# LEO_COTS_no_mult_rev1.net
KiCad netlist of a schematic drawn in Altium Designer
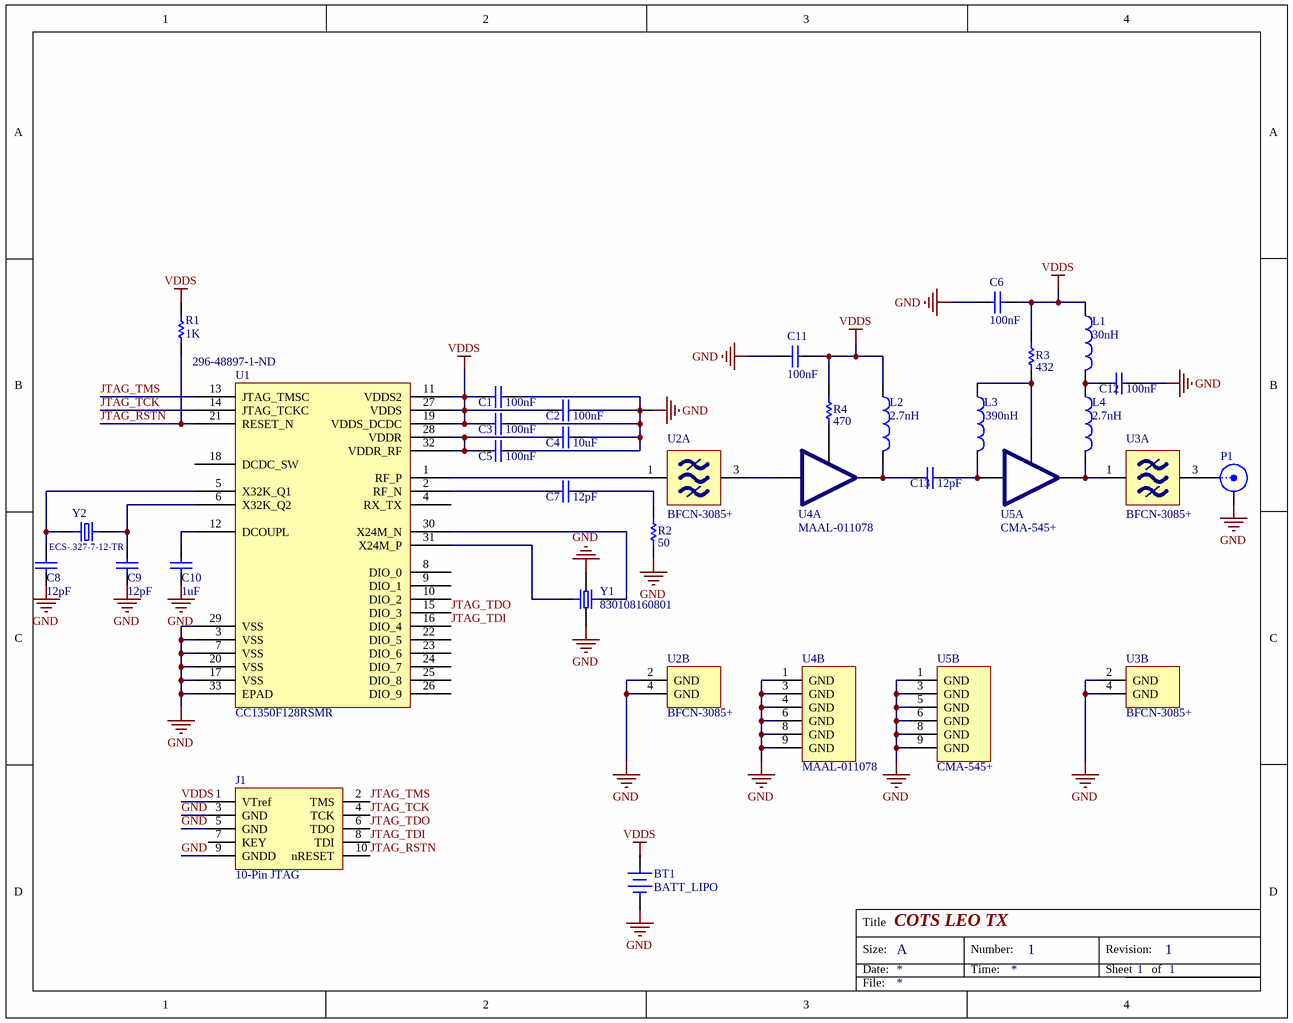
[diagram p0: LEO_COTS_no_mult_rev1.SchDoc]

(export (version "E")
  (design (tool "Eeschema 10.0.6"))
  (components
    (comp (ref "BT1")
      (value "BATT_LIPO")
      (footprint "LIPO_1cm_1cm")
      (libsource (lib "LEO_COTS_components") (part "BATT_LIPO"))
    )
    (comp (ref "C1")
      (value "100nF")
      (footprint "CAPC0603X04N")
      (description "CAP CER 100nF 0201")
      (fields (field (name "Comment") "CAP_0201"))
      (libsource (lib "LEO_COTS_components") (part "CAP_0201"))
    )
    (comp (ref "C2")
      (value "100nF")
      (footprint "CAPC0603X04N")
      (description "CAP CER 100nF 0201")
      (fields (field (name "Comment") "CAP_0201"))
      (libsource (lib "LEO_COTS_components") (part "CAP_0201"))
    )
    (comp (ref "C3")
      (value "100nF")
      (footprint "CAPC0603X04N")
      (description "CAP CER 100nF 0201")
      (fields (field (name "Comment") "CAP_0201"))
      (libsource (lib "LEO_COTS_components") (part "CAP_0201"))
    )
    (comp (ref "C4")
      (value "10uF")
      (footprint "CAPC1608X05N")
      (description "CAP CER 10uF 0603")
      (fields (field (name "Comment") "CAP_0603"))
      (libsource (lib "LEO_COTS_components") (part "CAP_0603"))
    )
    (comp (ref "C5")
      (value "100nF")
      (footprint "CAPC0603X04N")
      (description "CAP CER 100nF 0201")
      (fields (field (name "Comment") "CAP_0201"))
      (libsource (lib "LEO_COTS_components") (part "CAP_0201"))
    )
    (comp (ref "C6")
      (value "100nF")
      (footprint "CAPC0603X04N")
      (description "CAP CER 100nF 0201")
      (fields (field (name "Comment") "CAP_0201"))
      (libsource (lib "LEO_COTS_components") (part "CAP_0201"))
    )
    (comp (ref "C7")
      (value "12pF")
      (footprint "CAPC0603X04N")
      (description "CAP CER 12pF 0201")
      (fields (field (name "Comment") "CAP_0201"))
      (libsource (lib "LEO_COTS_components") (part "CAP_0201"))
    )
    (comp (ref "C8")
      (value "12pF")
      (footprint "CAPC0603X04N")
      (description "CAP CER 12pF 0201")
      (fields (field (name "Comment") "CAP_0201"))
      (libsource (lib "LEO_COTS_components") (part "CAP_0201"))
    )
    (comp (ref "C9")
      (value "12pF")
      (footprint "CAPC0603X04N")
      (description "CAP CER 12pF 0201")
      (fields (field (name "Comment") "CAP_0201"))
      (libsource (lib "LEO_COTS_components") (part "CAP_0201"))
    )
    (comp (ref "C10")
      (value "1uF")
      (footprint "CAPC0603X04N")
      (description "CAP CER 1uF 0201")
      (fields (field (name "Comment") "CAP_0201"))
      (libsource (lib "LEO_COTS_components") (part "CAP_0201"))
    )
    (comp (ref "C11")
      (value "100nF")
      (footprint "CAPC0603X04N")
      (description "CAP CER 100nF 0201")
      (fields (field (name "Comment") "CAP_0201"))
      (libsource (lib "LEO_COTS_components") (part "CAP_0201"))
    )
    (comp (ref "C12")
      (value "100nF")
      (footprint "CAPC0603X04N")
      (description "CAP CER 100nF 0201")
      (fields (field (name "Comment") "CAP_0201"))
      (libsource (lib "LEO_COTS_components") (part "CAP_0201"))
    )
    (comp (ref "C13")
      (value "12pF")
      (footprint "CAPC0603X04N")
      (description "CAP CER 12pF 0201")
      (fields (field (name "Comment") "CAP_0201"))
      (libsource (lib "LEO_COTS_components") (part "CAP_0201"))
    )
    (comp (ref "J1")
      (value "10-Pin JTAG")
      (footprint "FTSH-105-01-F-DV-007-K")
      (description "10-pin JTAG")
      (libsource (lib "LEO_COTS_components") (part "CM10"))
    )
    (comp (ref "L1")
      (value "30nH")
      (footprint "0402")
      (description "Inductor")
      (fields (field (name "PUBLISHER") "Altium Limited"))
      (libsource (lib "LEO_COTS_components") (part "Inductor"))
    )
    (comp (ref "L2")
      (value "2.7nH")
      (footprint "0402")
      (description "Inductor")
      (fields (field (name "PUBLISHER") "Altium Limited"))
      (libsource (lib "LEO_COTS_components") (part "Inductor"))
    )
    (comp (ref "L3")
      (value "390nH")
      (footprint "1608[0603]")
      (description "Inductor")
      (fields (field (name "PUBLISHER") "Altium Limited"))
      (libsource (lib "LEO_COTS_components") (part "Inductor"))
    )
    (comp (ref "L4")
      (value "2.7nH")
      (footprint "0402")
      (description "Inductor")
      (fields (field (name "PUBLISHER") "Altium Limited"))
      (libsource (lib "LEO_COTS_components") (part "Inductor"))
    )
    (comp (ref "P1")
      (value "1909763-1")
      (footprint "1909763-1")
      (description "CONN UMCC JACK STR 50OHM SMD")
      (libsource (lib "LEO_COTS_components") (part "1909763-1"))
    )
    (comp (ref "R1")
      (value "1K")
      (footprint "CAPC0603X04N")
      (description "RES 1K OHM 0201")
      (fields (field (name "Comment") "RES_0201") (field (name "PUBLISHER") "Altium Limited"))
      (libsource (lib "LEO_COTS_components") (part "Res Semi"))
    )
    (comp (ref "R2")
      (value "50")
      (footprint "CAPC0603X04N")
      (description "RES 50 OHM 0201")
      (fields (field (name "Comment") "RES_0201") (field (name "PUBLISHER") "Altium Limited"))
      (libsource (lib "LEO_COTS_components") (part "Res Semi"))
    )
    (comp (ref "R3")
      (value "432")
      (footprint "CAPC0603X04N")
      (description "RES 432 OHM 0201")
      (fields (field (name "Comment") "RES_0201") (field (name "PUBLISHER") "Altium Limited"))
      (libsource (lib "LEO_COTS_components") (part "Res Semi"))
    )
    (comp (ref "R4")
      (value "470")
      (footprint "CAPC0603X04N")
      (description "RES 50 OHM 0201")
      (fields (field (name "Comment") "RES_0201") (field (name "PUBLISHER") "Altium Limited"))
      (libsource (lib "LEO_COTS_components") (part "Res Semi"))
    )
    (comp (ref "U1")
      (value "CC1350F128RSMR")
      (footprint "QFN40P400X400X100-33N")
      (description "Ultra-Low-Power Dual-Band Wireless MCU")
      (fields (field (name "SUPPLIER PART NUMBER 1") "296-48897-1-ND"))
      (libsource (lib "LEO_COTS_components") (part "CC1350F128RSMR"))
    )
    (comp (ref "U2")
      (value "BFCN-3085+")
      (footprint "FV1206")
      (description "2800 to 3400 MHz Band-Pass Filter")
      (libsource (lib "LEO_COTS_components") (part "BFCN-3085+"))
    )
    (comp (ref "U3")
      (value "BFCN-3085+")
      (footprint "FV1206")
      (description "2800 to 3400 MHz Band-Pass Filter")
      (libsource (lib "LEO_COTS_components") (part "BFCN-3085+"))
    )
    (comp (ref "U4")
      (value "MAAL-011078")
      (footprint "PDFN-8")
      (description "Wideband LNA")
      (libsource (lib "LEO_COTS_components") (part "MAAL-011078"))
    )
    (comp (ref "U5")
      (value "CMA-545+")
      (footprint "DL1721")
      (description "Wideband LNA")
      (libsource (lib "LEO_COTS_components") (part "CMA-545+"))
    )
    (comp (ref "Y1")
      (value "830108160801")
      (footprint "LFXTAL081608")
      (description "24 MHz crystal")
      (fields (field (name "MP") "ECS-.327-7-12-TR"))
      (libsource (lib "LEO_COTS_components") (part "830108160801"))
    )
    (comp (ref "Y2")
      (value "ECS-.327-7-12-TR")
      (footprint "XTAL_ECS-.327-7-12-TR")
      (description "32.768 kHz SMD Crystal")
      (libsource (lib "LEO_COTS_components") (part "ECS-.327-7-12-TR"))
    )
  )
  (nets
    (net (code "1") (name "/JTAG_RSTN") (class "Default")
      (node (ref "J1") (pin "10") (pinfunction "nRESET_10") (pintype "passive"))
      (node (ref "R1") (pin "1") (pinfunction "1_1") (pintype "passive"))
      (node (ref "U1") (pin "21") (pinfunction "RESET_N_21") (pintype "passive"))
    )
    (net (code "2") (name "/JTAG_TCK") (class "Default")
      (node (ref "J1") (pin "4") (pinfunction "TCK_4") (pintype "passive"))
      (node (ref "U1") (pin "14") (pinfunction "JTAG_TCKC_14") (pintype "passive"))
    )
    (net (code "3") (name "/JTAG_TDI") (class "Default")
      (node (ref "J1") (pin "8") (pinfunction "TDI_8") (pintype "passive"))
      (node (ref "U1") (pin "16") (pinfunction "DIO_4_16") (pintype "passive"))
    )
    (net (code "4") (name "/JTAG_TDO") (class "Default")
      (node (ref "J1") (pin "6") (pinfunction "TDO_6") (pintype "passive"))
      (node (ref "U1") (pin "15") (pinfunction "DIO_3_15") (pintype "passive"))
    )
    (net (code "5") (name "/JTAG_TMS") (class "Default")
      (node (ref "J1") (pin "2") (pinfunction "TMS_2") (pintype "passive"))
      (node (ref "U1") (pin "13") (pinfunction "JTAG_TMSC_13") (pintype "passive"))
    )
    (net (code "6") (name "GND") (class "Default")
      (node (ref "BT1") (pin "2") (pinfunction "-_2") (pintype "passive"))
      (node (ref "C1") (pin "1") (pinfunction "1_1") (pintype "passive"))
      (node (ref "C10") (pin "1") (pinfunction "1_1") (pintype "passive"))
      (node (ref "C11") (pin "1") (pinfunction "1_1") (pintype "passive"))
      (node (ref "C12") (pin "1") (pinfunction "1_1") (pintype "passive"))
      (node (ref "C2") (pin "1") (pinfunction "1_1") (pintype "passive"))
      (node (ref "C3") (pin "1") (pinfunction "1_1") (pintype "passive"))
      (node (ref "C4") (pin "2") (pinfunction "2_2") (pintype "passive"))
      (node (ref "C5") (pin "1") (pinfunction "1_1") (pintype "passive"))
      (node (ref "C6") (pin "1") (pinfunction "1_1") (pintype "passive"))
      (node (ref "C8") (pin "1") (pinfunction "1_1") (pintype "passive"))
      (node (ref "C9") (pin "1") (pinfunction "1_1") (pintype "passive"))
      (node (ref "J1") (pin "3") (pinfunction "GND_3") (pintype "passive"))
      (node (ref "J1") (pin "5") (pinfunction "GND_5") (pintype "passive"))
      (node (ref "J1") (pin "9") (pinfunction "GNDD_9") (pintype "passive"))
      (node (ref "P1") (pin "2") (pinfunction "Y_2") (pintype "passive"))
      (node (ref "R2") (pin "1") (pinfunction "1_1") (pintype "passive"))
      (node (ref "U1") (pin "17") (pinfunction "VSS_17") (pintype "passive"))
      (node (ref "U1") (pin "20") (pinfunction "VSS_20") (pintype "passive"))
      (node (ref "U1") (pin "29") (pinfunction "VSS_29") (pintype "passive"))
      (node (ref "U1") (pin "3") (pinfunction "VSS_3") (pintype "passive"))
      (node (ref "U1") (pin "33") (pinfunction "EPAD_33") (pintype "passive"))
      (node (ref "U1") (pin "7") (pinfunction "VSS_7") (pintype "passive"))
      (node (ref "U2") (pin "2") (pinfunction "GND_2") (pintype "tri_state"))
      (node (ref "U2") (pin "4") (pinfunction "GND_4") (pintype "tri_state"))
      (node (ref "U3") (pin "2") (pinfunction "GND_2") (pintype "tri_state"))
      (node (ref "U3") (pin "4") (pinfunction "GND_4") (pintype "tri_state"))
      (node (ref "U4") (pin "1") (pinfunction "GND_1") (pintype "tri_state"))
      (node (ref "U4") (pin "3") (pinfunction "GND_3") (pintype "tri_state"))
      (node (ref "U4") (pin "4") (pinfunction "GND_4") (pintype "tri_state"))
      (node (ref "U4") (pin "6") (pinfunction "GND_6") (pintype "tri_state"))
      (node (ref "U4") (pin "8") (pinfunction "GND_8") (pintype "tri_state"))
      (node (ref "U4") (pin "9") (pinfunction "GND_9") (pintype "tri_state"))
      (node (ref "U5") (pin "1") (pinfunction "GND_1") (pintype "tri_state"))
      (node (ref "U5") (pin "3") (pinfunction "GND_3") (pintype "tri_state"))
      (node (ref "U5") (pin "5") (pinfunction "GND_5") (pintype "tri_state"))
      (node (ref "U5") (pin "6") (pinfunction "GND_6") (pintype "tri_state"))
      (node (ref "U5") (pin "8") (pinfunction "GND_8") (pintype "tri_state"))
      (node (ref "U5") (pin "9") (pinfunction "GND_9") (pintype "tri_state"))
      (node (ref "Y1") (pin "2") (pinfunction "2_2") (pintype "passive"))
      (node (ref "Y1") (pin "4") (pinfunction "4_4") (pintype "passive"))
    )
    (net (code "7") (name "Net-(C7-Pad1)") (class "Default")
      (node (ref "C7") (pin "1") (pinfunction "1_1") (pintype "passive"))
      (node (ref "R2") (pin "2") (pinfunction "2_2") (pintype "passive"))
    )
    (net (code "8") (name "Net-(C12-Pad2)") (class "Default")
      (node (ref "C12") (pin "2") (pinfunction "2_2") (pintype "passive"))
      (node (ref "L1") (pin "2") (pinfunction "2_2") (pintype "passive"))
      (node (ref "L4") (pin "1") (pinfunction "1_1") (pintype "passive"))
    )
    (net (code "9") (name "Net-(P1-X)") (class "Default")
      (node (ref "P1") (pin "1") (pinfunction "X_1") (pintype "passive"))
      (node (ref "U3") (pin "3") (pinfunction "OUT_3") (pintype "tri_state"))
    )
    (net (code "10") (name "Net-(U1-DCOUPL)") (class "Default")
      (node (ref "C10") (pin "2") (pinfunction "2_2") (pintype "passive"))
      (node (ref "U1") (pin "12") (pinfunction "DCOUPL_12") (pintype "passive"))
    )
    (net (code "11") (name "Net-(U1-RF_N)") (class "Default")
      (node (ref "C7") (pin "2") (pinfunction "2_2") (pintype "passive"))
      (node (ref "U1") (pin "2") (pinfunction "RF_N_2") (pintype "passive"))
    )
    (net (code "12") (name "Net-(U1-RF_P)") (class "Default")
      (node (ref "U1") (pin "1") (pinfunction "RF_P_1") (pintype "passive"))
      (node (ref "U2") (pin "1") (pinfunction "IN_1") (pintype "tri_state"))
    )
    (net (code "13") (name "Net-(U1-VDDR)") (class "Default")
      (node (ref "C4") (pin "1") (pinfunction "1_1") (pintype "passive"))
      (node (ref "C5") (pin "2") (pinfunction "2_2") (pintype "passive"))
      (node (ref "U1") (pin "28") (pinfunction "VDDR_28") (pintype "passive"))
      (node (ref "U1") (pin "32") (pinfunction "VDDR_RF_32") (pintype "passive"))
    )
    (net (code "14") (name "Net-(U1-X24M_N)") (class "Default")
      (node (ref "U1") (pin "30") (pinfunction "X24M_N_30") (pintype "passive"))
      (node (ref "Y1") (pin "3") (pinfunction "3_3") (pintype "passive"))
    )
    (net (code "15") (name "Net-(U1-X24M_P)") (class "Default")
      (node (ref "U1") (pin "31") (pinfunction "X24M_P_31") (pintype "passive"))
      (node (ref "Y1") (pin "1") (pinfunction "1_1") (pintype "passive"))
    )
    (net (code "16") (name "Net-(U1-X32K_Q1)") (class "Default")
      (node (ref "C8") (pin "2") (pinfunction "2_2") (pintype "passive"))
      (node (ref "U1") (pin "5") (pinfunction "X32K_Q1_5") (pintype "passive"))
      (node (ref "Y2") (pin "1") (pinfunction "1_1") (pintype "passive"))
    )
    (net (code "17") (name "Net-(U1-X32K_Q2)") (class "Default")
      (node (ref "C9") (pin "2") (pinfunction "2_2") (pintype "passive"))
      (node (ref "U1") (pin "6") (pinfunction "X32K_Q2_6") (pintype "passive"))
      (node (ref "Y2") (pin "2") (pinfunction "2_2") (pintype "passive"))
    )
    (net (code "18") (name "Net-(U2A-OUT)") (class "Default")
      (node (ref "U2") (pin "3") (pinfunction "OUT_3") (pintype "tri_state"))
      (node (ref "U4") (pin "2") (pinfunction "IN_2") (pintype "tri_state"))
    )
    (net (code "19") (name "Net-(U3A-IN)") (class "Default")
      (node (ref "L4") (pin "2") (pinfunction "2_2") (pintype "passive"))
      (node (ref "U3") (pin "1") (pinfunction "IN_1") (pintype "tri_state"))
      (node (ref "U5") (pin "7") (pinfunction "OUT_7") (pintype "tri_state"))
    )
    (net (code "20") (name "Net-(U4A-BIAS)") (class "Default")
      (node (ref "R4") (pin "1") (pinfunction "1_1") (pintype "passive"))
      (node (ref "U4") (pin "5") (pinfunction "BIAS_5") (pintype "tri_state"))
    )
    (net (code "21") (name "Net-(U4A-OUT)") (class "Default")
      (node (ref "C13") (pin "2") (pinfunction "2_2") (pintype "passive"))
      (node (ref "L2") (pin "2") (pinfunction "2_2") (pintype "passive"))
      (node (ref "U4") (pin "7") (pinfunction "OUT_7") (pintype "tri_state"))
    )
    (net (code "22") (name "Net-(U5A-BIAS)") (class "Default")
      (node (ref "L3") (pin "1") (pinfunction "1_1") (pintype "passive"))
      (node (ref "R3") (pin "1") (pinfunction "1_1") (pintype "passive"))
      (node (ref "U5") (pin "4") (pinfunction "BIAS_4") (pintype "tri_state"))
    )
    (net (code "23") (name "Net-(U5A-IN)") (class "Default")
      (node (ref "C13") (pin "1") (pinfunction "1_1") (pintype "passive"))
      (node (ref "L3") (pin "2") (pinfunction "2_2") (pintype "passive"))
      (node (ref "U5") (pin "2") (pinfunction "IN_2") (pintype "tri_state"))
    )
    (net (code "24") (name "VDDS") (class "Default")
      (node (ref "BT1") (pin "1") (pinfunction "+_1") (pintype "passive"))
      (node (ref "C1") (pin "2") (pinfunction "2_2") (pintype "passive"))
      (node (ref "C11") (pin "2") (pinfunction "2_2") (pintype "passive"))
      (node (ref "C2") (pin "2") (pinfunction "2_2") (pintype "passive"))
      (node (ref "C3") (pin "2") (pinfunction "2_2") (pintype "passive"))
      (node (ref "C6") (pin "2") (pinfunction "2_2") (pintype "passive"))
      (node (ref "J1") (pin "1") (pinfunction "VTref_1") (pintype "passive"))
      (node (ref "L1") (pin "1") (pinfunction "1_1") (pintype "passive"))
      (node (ref "L2") (pin "1") (pinfunction "1_1") (pintype "passive"))
      (node (ref "R1") (pin "2") (pinfunction "2_2") (pintype "passive"))
      (node (ref "R3") (pin "2") (pinfunction "2_2") (pintype "passive"))
      (node (ref "R4") (pin "2") (pinfunction "2_2") (pintype "passive"))
      (node (ref "U1") (pin "11") (pinfunction "VDDS2_11") (pintype "passive"))
      (node (ref "U1") (pin "19") (pinfunction "VDDS_DCDC_19") (pintype "passive"))
      (node (ref "U1") (pin "27") (pinfunction "VDDS_27") (pintype "passive"))
    )
    (net (code "25") (name "unconnected-(J1-KEY-Pad7)") (class "Default")
      (node (ref "J1") (pin "7") (pinfunction "KEY_7") (pintype "passive"))
    )
    (net (code "26") (name "unconnected-(U1-DCDC_SW-Pad18)") (class "Default")
      (node (ref "U1") (pin "18") (pinfunction "DCDC_SW_18") (pintype "passive"))
    )
    (net (code "27") (name "unconnected-(U1-DIO_0-Pad8)") (class "Default")
      (node (ref "U1") (pin "8") (pinfunction "DIO_0_8") (pintype "passive"))
    )
    (net (code "28") (name "unconnected-(U1-DIO_1-Pad9)") (class "Default")
      (node (ref "U1") (pin "9") (pinfunction "DIO_1_9") (pintype "passive"))
    )
    (net (code "29") (name "unconnected-(U1-DIO_2-Pad10)") (class "Default")
      (node (ref "U1") (pin "10") (pinfunction "DIO_2_10") (pintype "passive"))
    )
    (net (code "30") (name "unconnected-(U1-DIO_5-Pad22)") (class "Default")
      (node (ref "U1") (pin "22") (pinfunction "DIO_5_22") (pintype "passive"))
    )
    (net (code "31") (name "unconnected-(U1-DIO_6-Pad23)") (class "Default")
      (node (ref "U1") (pin "23") (pinfunction "DIO_6_23") (pintype "passive"))
    )
    (net (code "32") (name "unconnected-(U1-DIO_7-Pad24)") (class "Default")
      (node (ref "U1") (pin "24") (pinfunction "DIO_7_24") (pintype "passive"))
    )
    (net (code "33") (name "unconnected-(U1-DIO_8-Pad25)") (class "Default")
      (node (ref "U1") (pin "25") (pinfunction "DIO_8_25") (pintype "passive"))
    )
    (net (code "34") (name "unconnected-(U1-DIO_9-Pad26)") (class "Default")
      (node (ref "U1") (pin "26") (pinfunction "DIO_9_26") (pintype "passive"))
    )
    (net (code "35") (name "unconnected-(U1-RX_TX-Pad4)") (class "Default")
      (node (ref "U1") (pin "4") (pinfunction "RX_TX_4") (pintype "passive"))
    )
  )
)
